# QCPower_Rev_A_Sht2_BLDC_Controller.net
KiCad netlist of a schematic drawn in Altium Designer
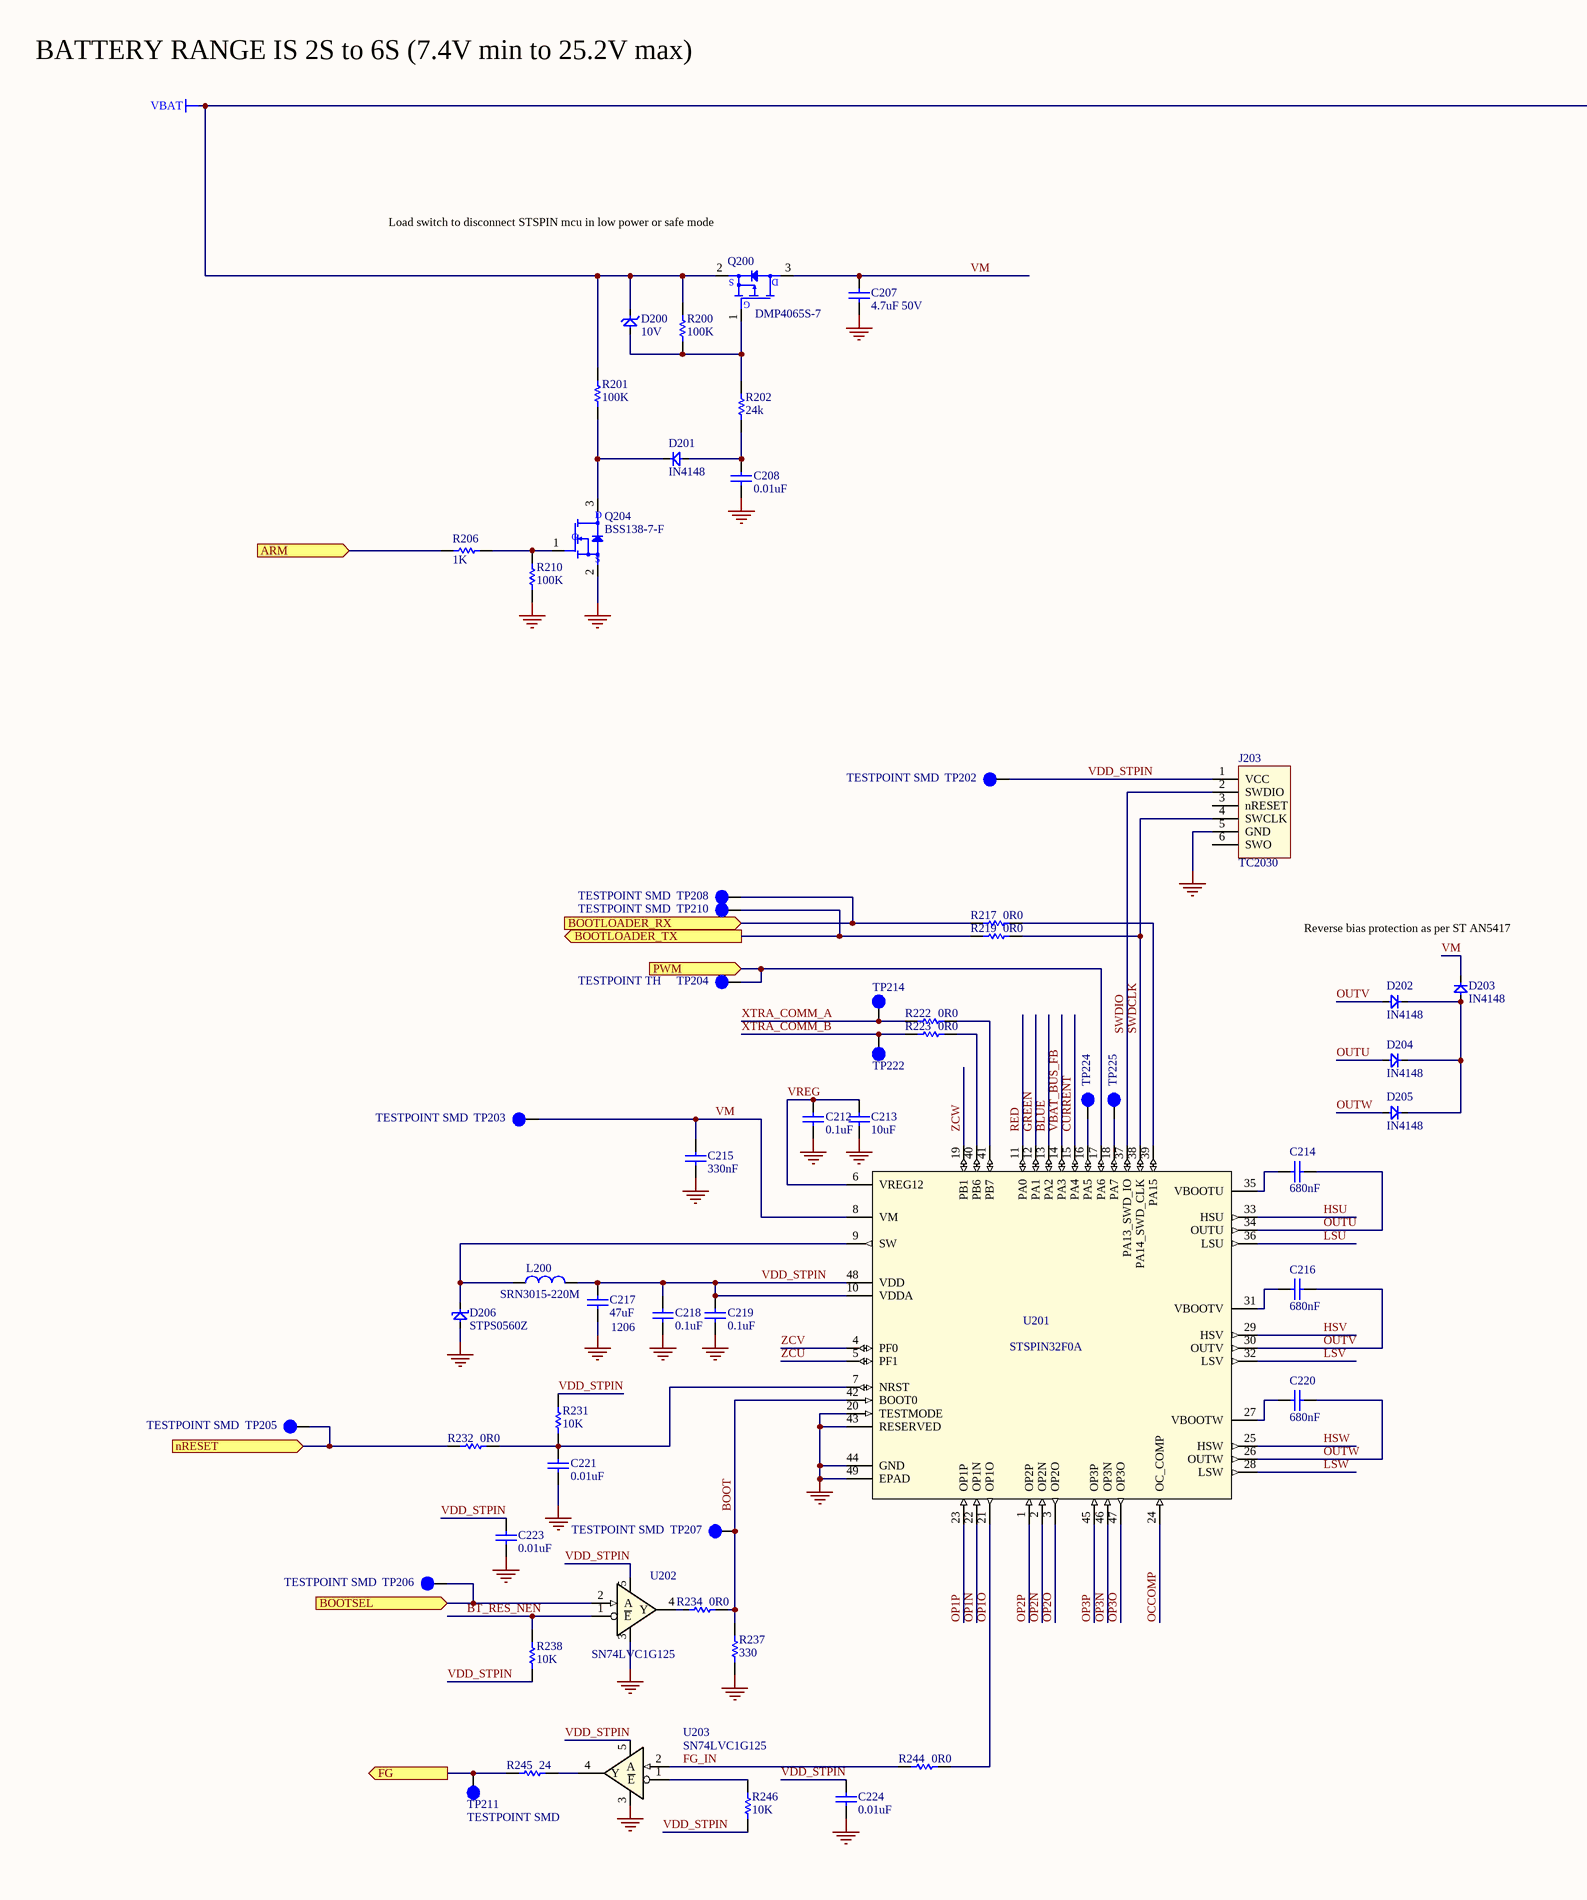
[diagram p0: QCPower Rev A Sht2 BLDC Controller.SchDoc, left]
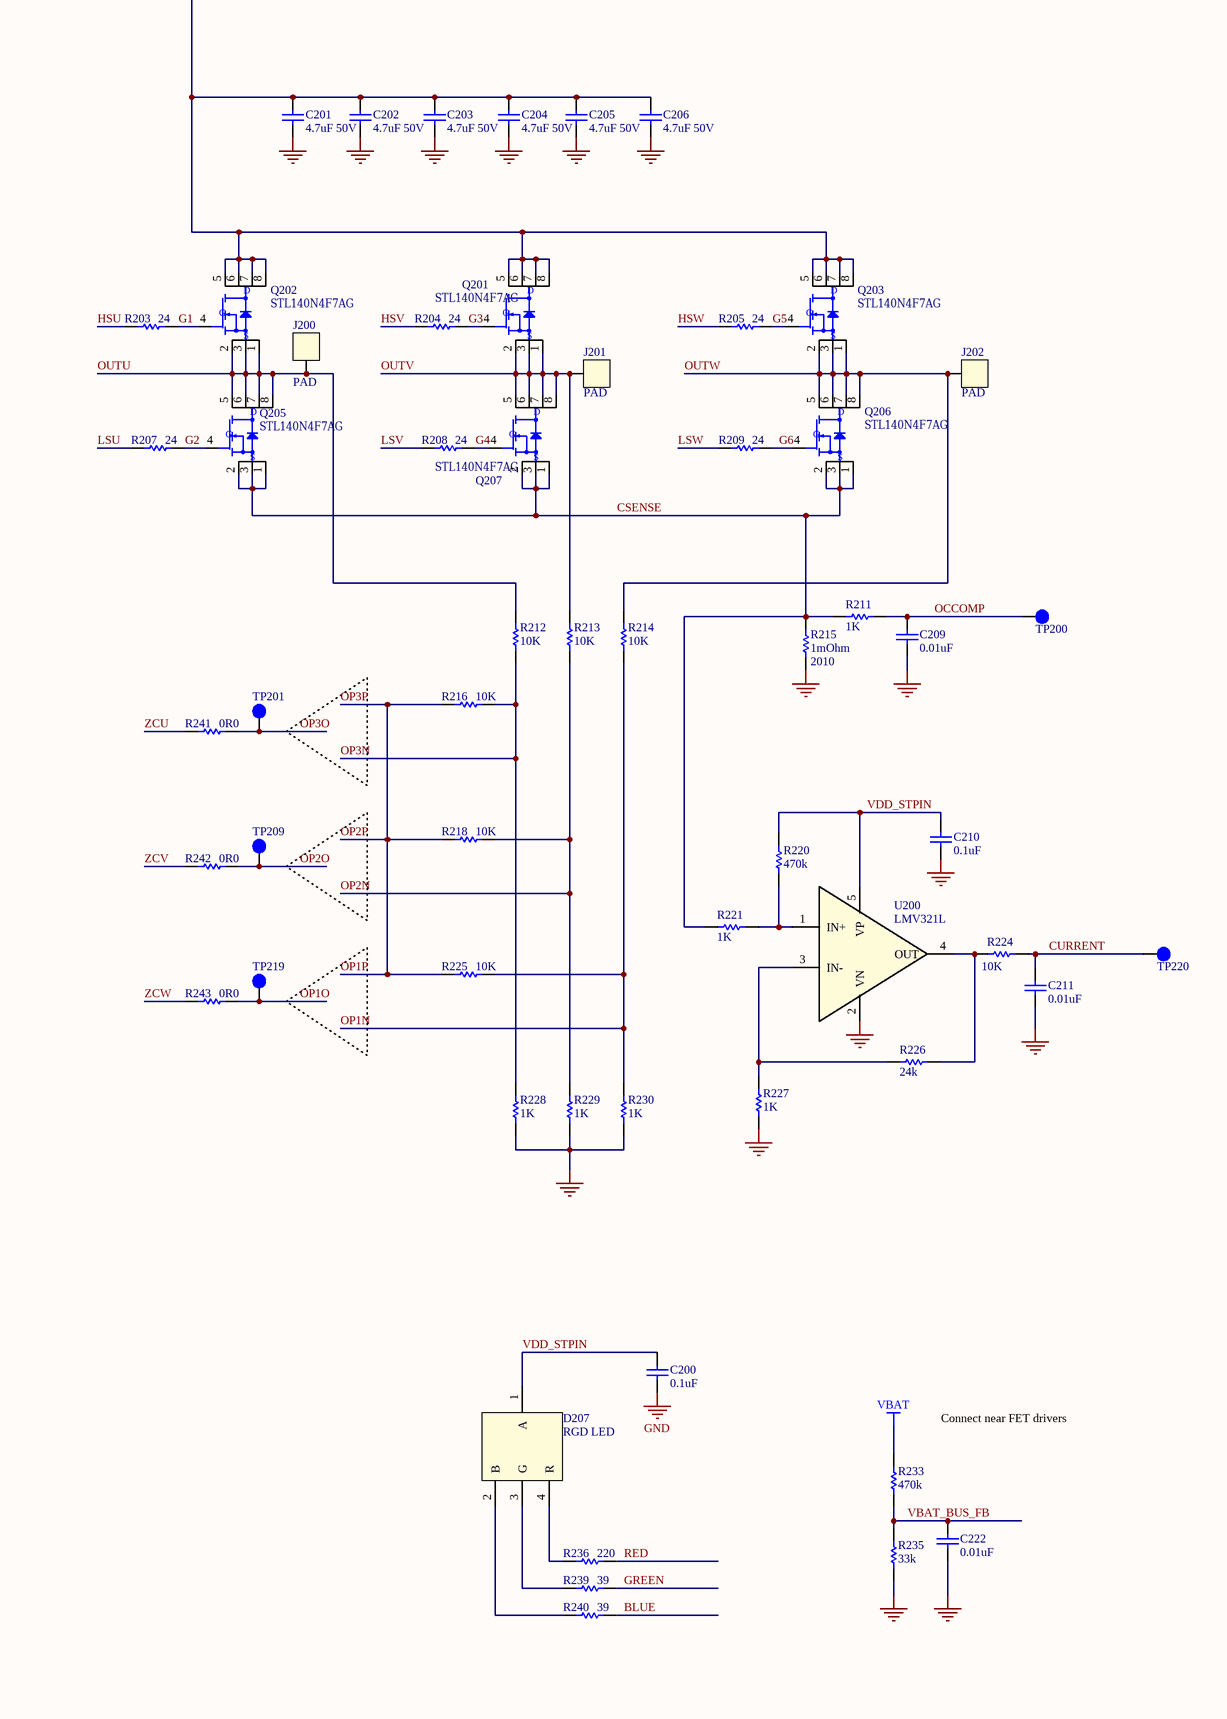
[diagram p1: QCPower Rev A Sht2 BLDC Controller.SchDoc, right]

(export (version "E")
  (design (tool "Eeschema 10.0.6"))
  (components
    (comp (ref "C200")
      (value "0.1uF")
      (footprint "SMD CAP 0402")
      (description "CAP CER 0.1UF 25V X7R 0402")
      (fields (field (name "2. MANUFACTURER PART NUMBER") "CC0402KRX7R8BB104"))
      (libsource (lib "SBCLib") (part "CAP MLCC SMD"))
    )
    (comp (ref "C201")
      (value "4.7uF 50V")
      (footprint "SMD CAP 0805")
      (description "CAP CER 4.7UF 50V X5R 0805")
      (fields (field (name "2. MANUFACTURER PART NUMBER") "CL21A475KBQNNNE"))
      (libsource (lib "SBCLib") (part "CAP MLCC SMD"))
    )
    (comp (ref "C202")
      (value "4.7uF 50V")
      (footprint "SMD CAP 0805")
      (description "CAP CER 4.7UF 50V X5R 0805")
      (fields (field (name "2. MANUFACTURER PART NUMBER") "CL21A475KBQNNNE"))
      (libsource (lib "SBCLib") (part "CAP MLCC SMD"))
    )
    (comp (ref "C203")
      (value "4.7uF 50V")
      (footprint "SMD CAP 0805")
      (description "CAP CER 4.7UF 50V X5R 0805")
      (fields (field (name "2. MANUFACTURER PART NUMBER") "CL21A475KBQNNNE"))
      (libsource (lib "SBCLib") (part "CAP MLCC SMD"))
    )
    (comp (ref "C204")
      (value "4.7uF 50V")
      (footprint "SMD CAP 0805")
      (description "CAP CER 4.7UF 50V X5R 0805")
      (fields (field (name "2. MANUFACTURER PART NUMBER") "CL21A475KBQNNNE"))
      (libsource (lib "SBCLib") (part "CAP MLCC SMD"))
    )
    (comp (ref "C205")
      (value "4.7uF 50V")
      (footprint "SMD CAP 0805")
      (description "CAP CER 4.7UF 50V X5R 0805")
      (fields (field (name "2. MANUFACTURER PART NUMBER") "CL21A475KBQNNNE"))
      (libsource (lib "SBCLib") (part "CAP MLCC SMD"))
    )
    (comp (ref "C206")
      (value "4.7uF 50V")
      (footprint "SMD CAP 0805")
      (description "CAP CER 4.7UF 50V X5R 0805")
      (fields (field (name "2. MANUFACTURER PART NUMBER") "CL21A475KBQNNNE"))
      (libsource (lib "SBCLib") (part "CAP MLCC SMD"))
    )
    (comp (ref "C207")
      (value "4.7uF 50V")
      (footprint "SMD CAP 0805")
      (description "CAP CER 4.7UF 50V X5R 0805")
      (fields (field (name "2. MANUFACTURER PART NUMBER") "CL21A475KBQNNNE"))
      (libsource (lib "SBCLib") (part "CAP MLCC SMD"))
    )
    (comp (ref "C208")
      (value "0.01uF")
      (footprint "SMD CAP 0402")
      (description "CAP CER 10000PF 16V X7R 0402")
      (fields (field (name "2. MANUFACTURER PART NUMBER") "0402B103K160CT"))
      (libsource (lib "SBCLib") (part "CAP MLCC SMD"))
    )
    (comp (ref "C209")
      (value "0.01uF")
      (footprint "SMD CAP 0402")
      (description "CAP CER 10000PF 16V X7R 0402")
      (fields (field (name "2. MANUFACTURER PART NUMBER") "0402B103K160CT"))
      (libsource (lib "SBCLib") (part "CAP MLCC SMD"))
    )
    (comp (ref "C210")
      (value "0.1uF")
      (footprint "SMD CAP 0402")
      (description "CAP CER 0.1UF 25V X7R 0402")
      (fields (field (name "2. MANUFACTURER PART NUMBER") "CC0402KRX7R8BB104"))
      (libsource (lib "SBCLib") (part "CAP MLCC SMD"))
    )
    (comp (ref "C211")
      (value "0.01uF")
      (footprint "SMD CAP 0402")
      (description "CAP CER 10000PF 16V X7R 0402")
      (fields (field (name "2. MANUFACTURER PART NUMBER") "0402B103K160CT"))
      (libsource (lib "SBCLib") (part "CAP MLCC SMD"))
    )
    (comp (ref "C212")
      (value "0.1uF")
      (footprint "SMD CAP 0402")
      (description "CAP CER 0.1UF 25V X7R 0402")
      (fields (field (name "2. MANUFACTURER PART NUMBER") "CC0402KRX7R8BB104"))
      (libsource (lib "SBCLib") (part "CAP MLCC SMD"))
    )
    (comp (ref "C213")
      (value "10uF")
      (footprint "SMD CAP 0805")
      (description "CAP CER 10UF 25V X5R 0805")
      (fields (field (name "2. MANUFACTURER PART NUMBER") "TMK212BBJ106KG-T"))
      (libsource (lib "SBCLib") (part "CAP MLCC SMD"))
    )
    (comp (ref "C214")
      (value "680nF")
      (footprint "SMD CAP 0603")
      (description "CAP CER 0.68UF 25V X7R 0603")
      (fields (field (name "2. MANUFACTURER PART NUMBER") "CGA3E1X7R1E684K080AC"))
      (libsource (lib "SBCLib") (part "CAP MLCC SMD"))
    )
    (comp (ref "C215")
      (value "330nF")
      (footprint "SMD CAP 0603")
      (description "CAP CER 0.33UF 50V X7R 0603")
      (fields (field (name "2. MANUFACTURER PART NUMBER") "C1608X7R1H334K080AC"))
      (libsource (lib "SBCLib") (part "CAP MLCC SMD"))
    )
    (comp (ref "C216")
      (value "680nF")
      (footprint "SMD CAP 0603")
      (description "CAP CER 0.68UF 25V X7R 0603")
      (fields (field (name "2. MANUFACTURER PART NUMBER") "CGA3E1X7R1E684K080AC"))
      (libsource (lib "SBCLib") (part "CAP MLCC SMD"))
    )
    (comp (ref "C217")
      (value "47uF")
      (footprint "SMD CAP 1206")
      (description "CAP CER 47UF 10V X5R 1206")
      (fields
        (field (name "2. MANUFACTURER PART NUMBER") "GRM31CR61A476ME15L")
        (field (name "4. PACKAGE") "1206")
      )
      (libsource (lib "SBCLib") (part "CAP MLCC SMD"))
    )
    (comp (ref "C218")
      (value "0.1uF")
      (footprint "SMD CAP 0402")
      (description "CAP CER 0.1UF 25V X7R 0402")
      (fields (field (name "2. MANUFACTURER PART NUMBER") "CC0402KRX7R8BB104"))
      (libsource (lib "SBCLib") (part "CAP MLCC SMD"))
    )
    (comp (ref "C219")
      (value "0.1uF")
      (footprint "SMD CAP 0402")
      (description "CAP CER 0.1UF 25V X7R 0402")
      (fields (field (name "2. MANUFACTURER PART NUMBER") "CC0402KRX7R8BB104"))
      (libsource (lib "SBCLib") (part "CAP MLCC SMD"))
    )
    (comp (ref "C220")
      (value "680nF")
      (footprint "SMD CAP 0603")
      (description "CAP CER 0.68UF 25V X7R 0603")
      (fields (field (name "2. MANUFACTURER PART NUMBER") "CGA3E1X7R1E684K080AC"))
      (libsource (lib "SBCLib") (part "CAP MLCC SMD"))
    )
    (comp (ref "C221")
      (value "0.01uF")
      (footprint "SMD CAP 0402")
      (description "CAP CER 10000PF 16V X7R 0402")
      (fields (field (name "2. MANUFACTURER PART NUMBER") "0402B103K160CT"))
      (libsource (lib "SBCLib") (part "CAP MLCC SMD"))
    )
    (comp (ref "C222")
      (value "0.01uF")
      (footprint "SMD CAP 0402")
      (description "CAP CER 10000PF 16V X7R 0402")
      (fields (field (name "2. MANUFACTURER PART NUMBER") "0402B103K160CT"))
      (libsource (lib "SBCLib") (part "CAP MLCC SMD"))
    )
    (comp (ref "C223")
      (value "0.01uF")
      (footprint "SMD CAP 0402")
      (description "CAP CER 10000PF 16V X7R 0402")
      (fields (field (name "2. MANUFACTURER PART NUMBER") "0402B103K160CT"))
      (libsource (lib "SBCLib") (part "CAP MLCC SMD"))
    )
    (comp (ref "C224")
      (value "0.01uF")
      (footprint "SMD CAP 0402")
      (description "CAP CER 10000PF 16V X7R 0402")
      (fields (field (name "2. MANUFACTURER PART NUMBER") "0402B103K160CT"))
      (libsource (lib "SBCLib") (part "CAP MLCC SMD"))
    )
    (comp (ref "D200")
      (value "10V")
      (footprint "DIODE SOD-523")
      (description "DIODE ZENER 10V 350MW SOD523")
      (fields (field (name "2. MANUFACTURER PART NUMBER") "BZT585B10T-7"))
      (libsource (lib "SBCLib") (part "DIODE ZENER"))
    )
    (comp (ref "D201")
      (value "IN4148")
      (footprint "DIODE SOD-523")
      (description "DIODE GEN PURP 75V 200MA SOD523F")
      (fields (field (name "2. MANUFACTURER PART NUMBER") "1N4148WT"))
      (libsource (lib "SBCLib") (part "DIODE STANDARD"))
    )
    (comp (ref "D202")
      (value "IN4148")
      (footprint "DIODE SOD-523")
      (description "DIODE GEN PURP 75V 200MA SOD523F")
      (fields (field (name "2. MANUFACTURER PART NUMBER") "1N4148WT"))
      (libsource (lib "SBCLib") (part "DIODE STANDARD"))
    )
    (comp (ref "D203")
      (value "IN4148")
      (footprint "DIODE SOD-523")
      (description "DIODE GEN PURP 75V 200MA SOD523F")
      (fields (field (name "2. MANUFACTURER PART NUMBER") "1N4148WT"))
      (libsource (lib "SBCLib") (part "DIODE STANDARD"))
    )
    (comp (ref "D204")
      (value "IN4148")
      (footprint "DIODE SOD-523")
      (description "DIODE GEN PURP 75V 200MA SOD523F")
      (fields (field (name "2. MANUFACTURER PART NUMBER") "1N4148WT"))
      (libsource (lib "SBCLib") (part "DIODE STANDARD"))
    )
    (comp (ref "D205")
      (value "IN4148")
      (footprint "DIODE SOD-523")
      (description "DIODE GEN PURP 75V 200MA SOD523F")
      (fields (field (name "2. MANUFACTURER PART NUMBER") "1N4148WT"))
      (libsource (lib "SBCLib") (part "DIODE STANDARD"))
    )
    (comp (ref "D206")
      (value "STPS0560Z")
      (footprint "DIODE SOD123")
      (description "DIODE SCHOTTKY 60V 500MA SOD123")
      (libsource (lib "SBCLib") (part "DIODE SCHOTTKY"))
    )
    (comp (ref "D207")
      (value "RGD LED")
      (footprint "PLCC-4 LED ASMB-MTB0-0A3A2")
      (description "LED RGB DIFFUSED 4PLCC SMD")
      (fields (field (name "2. MANUFACTURER PART NUMBER") "ASMB-MTB0-0A3A2"))
      (libsource (lib "SBCLib") (part "LED RGB DIFFUSED 4PLCC SMD"))
    )
    (comp (ref "J200")
      (value "PAD")
      (footprint "CONN SOLDER MOTOR")
      (description "CONN SOLDER MOTOR 7x5")
      (libsource (lib "SBCLib") (part "CONN SOLDER MOTOR 7x5"))
    )
    (comp (ref "J201")
      (value "PAD")
      (footprint "CONN SOLDER MOTOR")
      (description "CONN SOLDER MOTOR 7x5")
      (libsource (lib "") (part "CONN SOLDER MOTOR 7x5_1"))
    )
    (comp (ref "J202")
      (value "PAD")
      (footprint "CONN SOLDER MOTOR")
      (description "CONN SOLDER MOTOR 7x5")
      (libsource (lib "") (part "CONN SOLDER MOTOR 7x5_1"))
    )
    (comp (ref "J203")
      (value "TC2030")
      (footprint "tag-connect-6")
      (description "TC2030 PGM PADS")
      (fields (field (name "2. MANUFACTURER PART NUMBER") "NA"))
      (libsource (lib "MasterLiiiib") (part "TC2030"))
    )
    (comp (ref "L200")
      (value "SRN3015-220M")
      (footprint "INDUCTOR SRN3015-220M")
      (description "IND FIXED 22UH 600MA 622MOHM SMD")
      (libsource (lib "SBCLib") (part "INDUCTOR"))
    )
    (comp (ref "Q200")
      (value "DMP4065S-7")
      (footprint "SOT-23-3")
      (description "TRANS FET P-CH 40V 2.4A SOT23-3")
      (libsource (lib "SBCLib") (part "TRANS FET P-CH 40V 2.4A SOT23-3"))
    )
    (comp (ref "Q201")
      (value "STL140N4F7AG‎")
      (footprint "PowerFLAT 5x6")
      (description "MOSFET N-CH 40V 120A POWERFLAT")
      (libsource (lib "SBCLib") (part "TRANS FET N-CH 60V 145A 8PWRFLAT STL140N6F7"))
    )
    (comp (ref "Q202")
      (value "STL140N4F7AG‎")
      (footprint "PowerFLAT 5x6")
      (description "MOSFET N-CH 40V 120A POWERFLAT")
      (libsource (lib "SBCLib") (part "TRANS FET N-CH 60V 145A 8PWRFLAT STL140N6F7"))
    )
    (comp (ref "Q203")
      (value "STL140N4F7AG‎")
      (footprint "PowerFLAT 5x6")
      (description "MOSFET N-CH 40V 120A POWERFLAT")
      (libsource (lib "SBCLib") (part "TRANS FET N-CH 60V 145A 8PWRFLAT STL140N6F7"))
    )
    (comp (ref "Q204")
      (value "BSS138-7-F")
      (footprint "SOT-23-3")
      (description "TRANS FET N-CH 50V 200MA SOT23-3 BSS138-7-F")
      (libsource (lib "SBCLib") (part "TRANS FET N-CH 50V 200MA SOT23-3 BSS138-7-F"))
    )
    (comp (ref "Q205")
      (value "STL140N4F7AG‎")
      (footprint "PowerFLAT 5x6")
      (description "MOSFET N-CH 40V 120A POWERFLAT")
      (libsource (lib "SBCLib") (part "TRANS FET N-CH 60V 145A 8PWRFLAT STL140N6F7"))
    )
    (comp (ref "Q206")
      (value "STL140N4F7AG‎")
      (footprint "PowerFLAT 5x6")
      (description "MOSFET N-CH 40V 120A POWERFLAT")
      (libsource (lib "SBCLib") (part "TRANS FET N-CH 60V 145A 8PWRFLAT STL140N6F7"))
    )
    (comp (ref "Q207")
      (value "STL140N4F7AG‎")
      (footprint "PowerFLAT 5x6")
      (description "MOSFET N-CH 40V 120A POWERFLAT")
      (libsource (lib "SBCLib") (part "TRANS FET N-CH 60V 145A 8PWRFLAT STL140N6F7"))
    )
    (comp (ref "R200")
      (value "100K")
      (footprint "SMD RES 0402")
      (description "RES SMD 100K OHM 1% 1/16W 0402")
      (fields (field (name "2. MANUFACTURER PART NUMBER") "RC0402FR-07100KL"))
      (libsource (lib "SBCLib") (part "RES SMD"))
    )
    (comp (ref "R201")
      (value "100K")
      (footprint "SMD RES 0402")
      (description "RES SMD 100K OHM 1% 1/16W 0402")
      (fields (field (name "2. MANUFACTURER PART NUMBER") "RC0402FR-07100KL"))
      (libsource (lib "SBCLib") (part "RES SMD"))
    )
    (comp (ref "R202")
      (value "24k")
      (footprint "SMD RES 0402")
      (description "RES SMD 24K OHM 1% 1/16W 0402")
      (fields (field (name "2. MANUFACTURER PART NUMBER") "RC0402FR-0724KL"))
      (libsource (lib "SBCLib") (part "RES SMD"))
    )
    (comp (ref "R203")
      (value "24")
      (footprint "SMD RES 0402")
      (description "RES SMD 24 OHM 5% 1/10W 0402")
      (fields (field (name "2. MANUFACTURER PART NUMBER") "ERJ-2GEJ240X"))
      (libsource (lib "SBCLib") (part "RES SMD"))
    )
    (comp (ref "R204")
      (value "24")
      (footprint "SMD RES 0402")
      (description "RES SMD 24 OHM 5% 1/10W 0402")
      (fields (field (name "2. MANUFACTURER PART NUMBER") "ERJ-2GEJ240X"))
      (libsource (lib "SBCLib") (part "RES SMD"))
    )
    (comp (ref "R205")
      (value "24")
      (footprint "SMD RES 0402")
      (description "RES SMD 24 OHM 5% 1/10W 0402")
      (fields (field (name "2. MANUFACTURER PART NUMBER") "ERJ-2GEJ240X"))
      (libsource (lib "SBCLib") (part "RES SMD"))
    )
    (comp (ref "R206")
      (value "1K")
      (footprint "SMD RES 0402")
      (description "RES SMD 1K OHM 1% 1/16W 0402")
      (fields (field (name "2. MANUFACTURER PART NUMBER") "RC0402FR-071KL"))
      (libsource (lib "SBCLib") (part "RES SMD"))
    )
    (comp (ref "R207")
      (value "24")
      (footprint "SMD RES 0402")
      (description "RES SMD 24 OHM 5% 1/10W 0402")
      (fields (field (name "2. MANUFACTURER PART NUMBER") "ERJ-2GEJ240X"))
      (libsource (lib "SBCLib") (part "RES SMD"))
    )
    (comp (ref "R208")
      (value "24")
      (footprint "SMD RES 0402")
      (description "RES SMD 24 OHM 5% 1/10W 0402")
      (fields (field (name "2. MANUFACTURER PART NUMBER") "ERJ-2GEJ240X"))
      (libsource (lib "SBCLib") (part "RES SMD"))
    )
    (comp (ref "R209")
      (value "24")
      (footprint "SMD RES 0402")
      (description "RES SMD 24 OHM 5% 1/10W 0402")
      (fields (field (name "2. MANUFACTURER PART NUMBER") "ERJ-2GEJ240X"))
      (libsource (lib "SBCLib") (part "RES SMD"))
    )
    (comp (ref "R210")
      (value "100K")
      (footprint "SMD RES 0402")
      (description "RES SMD 100K OHM 1% 1/16W 0402")
      (fields (field (name "2. MANUFACTURER PART NUMBER") "RC0402FR-07100KL"))
      (libsource (lib "SBCLib") (part "RES SMD"))
    )
    (comp (ref "R211")
      (value "1K")
      (footprint "SMD RES 0402")
      (description "RES SMD 1K OHM 1% 1/16W 0402")
      (fields (field (name "2. MANUFACTURER PART NUMBER") "RC0402FR-071KL"))
      (libsource (lib "SBCLib") (part "RES SMD"))
    )
    (comp (ref "R212")
      (value "10K")
      (footprint "SMD RES 0402")
      (description "RES SMD 10K OHM 1% 1/16W 0402")
      (fields (field (name "2. MANUFACTURER PART NUMBER") "RC0402FR-0710KL"))
      (libsource (lib "SBCLib") (part "RES SMD"))
    )
    (comp (ref "R213")
      (value "10K")
      (footprint "SMD RES 0402")
      (description "RES SMD 10K OHM 1% 1/16W 0402")
      (fields (field (name "2. MANUFACTURER PART NUMBER") "RC0402FR-0710KL"))
      (libsource (lib "SBCLib") (part "RES SMD"))
    )
    (comp (ref "R214")
      (value "10K")
      (footprint "SMD RES 0402")
      (description "RES SMD 10K OHM 1% 1/16W 0402")
      (fields (field (name "2. MANUFACTURER PART NUMBER") "RC0402FR-0710KL"))
      (libsource (lib "SBCLib") (part "RES SMD"))
    )
    (comp (ref "R215")
      (value "1mOhm")
      (footprint "SMD RES 2010")
      (description "RES 0.001 OHM 1% 1.5W 2010")
      (fields
        (field (name "2. MANUFACTURER PART NUMBER") "CSNL2010FT1L00")
        (field (name "4. PACKAGE") "2010")
      )
      (libsource (lib "SBCLib") (part "RES SMD"))
    )
    (comp (ref "R216")
      (value "10K")
      (footprint "SMD RES 0402")
      (description "RES SMD 10K OHM 1% 1/16W 0402")
      (fields (field (name "2. MANUFACTURER PART NUMBER") "RC0402FR-0710KL"))
      (libsource (lib "SBCLib") (part "RES SMD"))
    )
    (comp (ref "R217")
      (value "0R0")
      (footprint "SMD RES 0402")
      (description "RES SMD 0 OHM JUMPER 1/16W 0402")
      (fields (field (name "2. MANUFACTURER PART NUMBER") "RC0402FR-070RL"))
      (libsource (lib "SBCLib") (part "RES SMD"))
    )
    (comp (ref "R218")
      (value "10K")
      (footprint "SMD RES 0402")
      (description "RES SMD 10K OHM 1% 1/16W 0402")
      (fields (field (name "2. MANUFACTURER PART NUMBER") "RC0402FR-0710KL"))
      (libsource (lib "SBCLib") (part "RES SMD"))
    )
    (comp (ref "R219")
      (value "0R0")
      (footprint "SMD RES 0402")
      (description "RES SMD 0 OHM JUMPER 1/16W 0402")
      (fields (field (name "2. MANUFACTURER PART NUMBER") "RC0402FR-070RL"))
      (libsource (lib "SBCLib") (part "RES SMD"))
    )
    (comp (ref "R220")
      (value "470k")
      (footprint "SMD RES 0402")
      (description "RES SMD 470K OHM 1% 1/16W 0402")
      (fields (field (name "2. MANUFACTURER PART NUMBER") "RC0402FR-07470KL"))
      (libsource (lib "SBCLib") (part "RES SMD"))
    )
    (comp (ref "R221")
      (value "1K")
      (footprint "SMD RES 0402")
      (description "RES SMD 1K OHM 1% 1/16W 0402")
      (fields (field (name "2. MANUFACTURER PART NUMBER") "RC0402FR-071KL"))
      (libsource (lib "SBCLib") (part "RES SMD"))
    )
    (comp (ref "R222")
      (value "0R0")
      (footprint "SMD RES 0402")
      (description "RES SMD 0 OHM JUMPER 1/16W 0402")
      (fields (field (name "2. MANUFACTURER PART NUMBER") "RC0402FR-070RL"))
      (libsource (lib "SBCLib") (part "RES SMD"))
    )
    (comp (ref "R223")
      (value "0R0")
      (footprint "SMD RES 0402")
      (description "RES SMD 0 OHM JUMPER 1/16W 0402")
      (fields (field (name "2. MANUFACTURER PART NUMBER") "RC0402FR-070RL"))
      (libsource (lib "SBCLib") (part "RES SMD"))
    )
    (comp (ref "R224")
      (value "10K")
      (footprint "SMD RES 0402")
      (description "RES SMD 10K OHM 1% 1/16W 0402")
      (fields (field (name "2. MANUFACTURER PART NUMBER") "RC0402FR-0710KL"))
      (libsource (lib "SBCLib") (part "RES SMD"))
    )
    (comp (ref "R225")
      (value "10K")
      (footprint "SMD RES 0402")
      (description "RES SMD 10K OHM 1% 1/16W 0402")
      (fields (field (name "2. MANUFACTURER PART NUMBER") "RC0402FR-0710KL"))
      (libsource (lib "SBCLib") (part "RES SMD"))
    )
    (comp (ref "R226")
      (value "24k")
      (footprint "SMD RES 0402")
      (description "RES SMD 24K OHM 1% 1/16W 0402")
      (fields (field (name "2. MANUFACTURER PART NUMBER") "RC0402FR-0724KL"))
      (libsource (lib "SBCLib") (part "RES SMD"))
    )
    (comp (ref "R227")
      (value "1K")
      (footprint "SMD RES 0402")
      (description "RES SMD 1K OHM 1% 1/16W 0402")
      (fields (field (name "2. MANUFACTURER PART NUMBER") "RC0402FR-071KL"))
      (libsource (lib "SBCLib") (part "RES SMD"))
    )
    (comp (ref "R228")
      (value "1K")
      (footprint "SMD RES 0402")
      (description "RES SMD 1K OHM 1% 1/16W 0402")
      (fields (field (name "2. MANUFACTURER PART NUMBER") "RC0402FR-071KL"))
      (libsource (lib "SBCLib") (part "RES SMD"))
    )
    (comp (ref "R229")
      (value "1K")
      (footprint "SMD RES 0402")
      (description "RES SMD 1K OHM 1% 1/16W 0402")
      (fields (field (name "2. MANUFACTURER PART NUMBER") "RC0402FR-071KL"))
      (libsource (lib "SBCLib") (part "RES SMD"))
    )
    (comp (ref "R230")
      (value "1K")
      (footprint "SMD RES 0402")
      (description "RES SMD 1K OHM 1% 1/16W 0402")
      (fields (field (name "2. MANUFACTURER PART NUMBER") "RC0402FR-071KL"))
      (libsource (lib "SBCLib") (part "RES SMD"))
    )
    (comp (ref "R231")
      (value "10K")
      (footprint "SMD RES 0402")
      (description "RES SMD 10K OHM 1% 1/16W 0402")
      (fields (field (name "2. MANUFACTURER PART NUMBER") "RC0402FR-0710KL"))
      (libsource (lib "SBCLib") (part "RES SMD"))
    )
    (comp (ref "R232")
      (value "0R0")
      (footprint "SMD RES 0402")
      (description "RES SMD 0 OHM JUMPER 1/16W 0402")
      (fields (field (name "2. MANUFACTURER PART NUMBER") "RC0402FR-070RL"))
      (libsource (lib "SBCLib") (part "RES SMD"))
    )
    (comp (ref "R233")
      (value "470k")
      (footprint "SMD RES 0402")
      (description "RES SMD 470K OHM 1% 1/16W 0402")
      (fields (field (name "2. MANUFACTURER PART NUMBER") "RC0402FR-07470KL"))
      (libsource (lib "SBCLib") (part "RES SMD"))
    )
    (comp (ref "R234")
      (value "0R0")
      (footprint "SMD RES 0402")
      (description "RES SMD 0 OHM JUMPER 1/16W 0402")
      (fields (field (name "2. MANUFACTURER PART NUMBER") "RC0402FR-070RL"))
      (libsource (lib "SBCLib") (part "RES SMD"))
    )
    (comp (ref "R235")
      (value "33k")
      (footprint "SMD RES 0402")
      (description "RES SMD 33K OHM 1% 1/16W 0402")
      (fields (field (name "2. MANUFACTURER PART NUMBER") "RC0402FR-0733KL"))
      (libsource (lib "SBCLib") (part "RES SMD"))
    )
    (comp (ref "R236")
      (value "220")
      (footprint "SMD RES 0402")
      (description "RES SMD 220 OHM 5% 1/16W 0402")
      (fields (field (name "2. MANUFACTURER PART NUMBER") "RC0402JR-07220RL"))
      (libsource (lib "SBCLib") (part "RES SMD"))
    )
    (comp (ref "R237")
      (value "330")
      (footprint "SMD RES 0402")
      (description "RES SMD 330 OHM 5% 1/16W 0402")
      (fields (field (name "2. MANUFACTURER PART NUMBER") "RC0402JR-07330RL"))
      (libsource (lib "SBCLib") (part "RES SMD"))
    )
    (comp (ref "R238")
      (value "10K")
      (footprint "SMD RES 0402")
      (description "RES SMD 10K OHM 1% 1/16W 0402")
      (fields (field (name "2. MANUFACTURER PART NUMBER") "RC0402FR-0710KL"))
      (libsource (lib "SBCLib") (part "RES SMD"))
    )
    (comp (ref "R239")
      (value "39")
      (footprint "SMD RES 0402")
      (description "RES SMD 39 OHM 5% 1/16W 0402")
      (fields (field (name "2. MANUFACTURER PART NUMBER") "RC0402JR-0739RL"))
      (libsource (lib "SBCLib") (part "RES SMD"))
    )
    (comp (ref "R240")
      (value "39")
      (footprint "SMD RES 0402")
      (description "RES SMD 39 OHM 5% 1/16W 0402")
      (fields (field (name "2. MANUFACTURER PART NUMBER") "RC0402JR-0739RL"))
      (libsource (lib "SBCLib") (part "RES SMD"))
    )
    (comp (ref "R241")
      (value "0R0")
      (footprint "SMD RES 0402")
      (description "RES SMD 0 OHM JUMPER 1/16W 0402")
      (fields (field (name "2. MANUFACTURER PART NUMBER") "RC0402FR-070RL"))
      (libsource (lib "SBCLib") (part "RES SMD"))
    )
    (comp (ref "R242")
      (value "0R0")
      (footprint "SMD RES 0402")
      (description "RES SMD 0 OHM JUMPER 1/16W 0402")
      (fields (field (name "2. MANUFACTURER PART NUMBER") "RC0402FR-070RL"))
      (libsource (lib "SBCLib") (part "RES SMD"))
    )
    (comp (ref "R243")
      (value "0R0")
      (footprint "SMD RES 0402")
      (description "RES SMD 0 OHM JUMPER 1/16W 0402")
      (fields (field (name "2. MANUFACTURER PART NUMBER") "RC0402FR-070RL"))
      (libsource (lib "SBCLib") (part "RES SMD"))
    )
    (comp (ref "R244")
      (value "0R0")
      (footprint "SMD RES 0402")
      (description "RES SMD 0 OHM JUMPER 1/16W 0402")
      (fields (field (name "2. MANUFACTURER PART NUMBER") "RC0402FR-070RL"))
      (libsource (lib "SBCLib") (part "RES SMD"))
    )
    (comp (ref "R245")
      (value "24")
      (footprint "SMD RES 0402")
      (description "RES SMD 24 OHM 5% 1/10W 0402")
      (fields (field (name "2. MANUFACTURER PART NUMBER") "ERJ-2GEJ240X"))
      (libsource (lib "SBCLib") (part "RES SMD"))
    )
    (comp (ref "R246")
      (value "10K")
      (footprint "SMD RES 0402")
      (description "RES SMD 10K OHM 1% 1/16W 0402")
      (fields (field (name "2. MANUFACTURER PART NUMBER") "RC0402FR-0710KL"))
      (libsource (lib "SBCLib") (part "RES SMD"))
    )
    (comp (ref "TP200")
      (value "TESTPOINT SMD")
      (footprint "TESTPOINT 0.5mm DIA")
      (description "TESTPOINT SMD PAD")
      (libsource (lib "SBCLib") (part "TESTPOINT PAD"))
    )
    (comp (ref "TP201")
      (value "TESTPOINT SMD")
      (footprint "TESTPOINT 0.5mm DIA")
      (description "TESTPOINT SMD PAD")
      (libsource (lib "SBCLib") (part "TESTPOINT PAD"))
    )
    (comp (ref "TP202")
      (value "TESTPOINT SMD")
      (footprint "TESTPOINT 0.5mm DIA")
      (description "TESTPOINT SMD PAD")
      (libsource (lib "SBCLib") (part "TESTPOINT PAD"))
    )
    (comp (ref "TP203")
      (value "TESTPOINT SMD")
      (footprint "TESTPOINT 0.5mm DIA")
      (description "TESTPOINT SMD PAD")
      (libsource (lib "SBCLib") (part "TESTPOINT PAD"))
    )
    (comp (ref "TP204")
      (value "TESTPOINT TH")
      (footprint "TESTPOINT TH")
      (description "TESTPOINT TH KEYSTONE")
      (fields (field (name "2. MANUFACTURER PART NUMBER") "5002"))
      (libsource (lib "SBCLib") (part "TESTPOINT TH"))
    )
    (comp (ref "TP205")
      (value "TESTPOINT SMD")
      (footprint "TESTPOINT 0.5mm DIA")
      (description "TESTPOINT SMD PAD")
      (libsource (lib "SBCLib") (part "TESTPOINT PAD"))
    )
    (comp (ref "TP206")
      (value "TESTPOINT SMD")
      (footprint "TESTPOINT 0.5mm DIA")
      (description "TESTPOINT SMD PAD")
      (libsource (lib "SBCLib") (part "TESTPOINT PAD"))
    )
    (comp (ref "TP207")
      (value "TESTPOINT SMD")
      (footprint "TESTPOINT 0.5mm DIA")
      (description "TESTPOINT SMD PAD")
      (libsource (lib "SBCLib") (part "TESTPOINT PAD"))
    )
    (comp (ref "TP208")
      (value "TESTPOINT SMD")
      (footprint "TESTPOINT 0.5mm DIA")
      (description "TESTPOINT SMD PAD")
      (libsource (lib "SBCLib") (part "TESTPOINT PAD"))
    )
    (comp (ref "TP209")
      (value "TESTPOINT SMD")
      (footprint "TESTPOINT 0.5mm DIA")
      (description "TESTPOINT SMD PAD")
      (libsource (lib "SBCLib") (part "TESTPOINT PAD"))
    )
    (comp (ref "TP210")
      (value "TESTPOINT SMD")
      (footprint "TESTPOINT 0.5mm DIA")
      (description "TESTPOINT SMD PAD")
      (libsource (lib "SBCLib") (part "TESTPOINT PAD"))
    )
    (comp (ref "TP211")
      (value "TESTPOINT SMD")
      (footprint "TESTPOINT 0.5mm DIA")
      (description "TESTPOINT SMD PAD")
      (libsource (lib "SBCLib") (part "TESTPOINT PAD"))
    )
    (comp (ref "TP214")
      (value "TESTPOINT SMD")
      (footprint "TESTPOINT 0.5mm DIA")
      (description "TESTPOINT SMD PAD")
      (libsource (lib "SBCLib") (part "TESTPOINT PAD"))
    )
    (comp (ref "TP219")
      (value "TESTPOINT SMD")
      (footprint "TESTPOINT 0.5mm DIA")
      (description "TESTPOINT SMD PAD")
      (libsource (lib "SBCLib") (part "TESTPOINT PAD"))
    )
    (comp (ref "TP220")
      (value "TESTPOINT SMD")
      (footprint "TESTPOINT 0.5mm DIA")
      (description "TESTPOINT SMD PAD")
      (libsource (lib "SBCLib") (part "TESTPOINT PAD"))
    )
    (comp (ref "TP222")
      (value "TESTPOINT SMD")
      (footprint "TESTPOINT 0.5mm DIA")
      (description "TESTPOINT SMD PAD")
      (libsource (lib "SBCLib") (part "TESTPOINT PAD"))
    )
    (comp (ref "TP224")
      (value "TESTPOINT SMD")
      (footprint "TESTPOINT 0.5mm DIA")
      (description "TESTPOINT SMD PAD")
      (libsource (lib "SBCLib") (part "TESTPOINT PAD"))
    )
    (comp (ref "TP225")
      (value "TESTPOINT SMD")
      (footprint "TESTPOINT 0.5mm DIA")
      (description "TESTPOINT SMD PAD")
      (libsource (lib "SBCLib") (part "TESTPOINT PAD"))
    )
    (comp (ref "U200")
      (value "LMV321L")
      (footprint "SOT-23-5")
      (description "IC OPAMP GP 1 CIRCUIT SOT23-5")
      (fields (field (name "2. MANUFACTURER PART NUMBER") "LMV321LILT"))
      (libsource (lib "SBCLib") (part "IC OPAMP GP 1 CIRCUIT SOT23-5"))
    )
    (comp (ref "U201")
      (value "STSPIN32F0A")
      (footprint "VQFN-48 7x7")
      (description "IC BLDC CONTROLLER STSPIN32F0A")
      (libsource (lib "SBCLib") (part "IC BLDC CONTROLLER STSPIN32F0A"))
    )
    (comp (ref "U202")
      (value "SN74LVC1G125")
      (footprint "SC70-5")
      (description "IC BUF TRI-STATE NON-INVERT 5.5V SC70-5")
      (fields (field (name "2. MANUFACTURER PART NUMBER") "SN74LVC1G125DCKR"))
      (libsource (lib "SBCLib") (part "IC BUF TRI-STATE NON-INVERT 5.5V SC70-5"))
    )
    (comp (ref "U203")
      (value "SN74LVC1G125")
      (footprint "SC70-5")
      (description "IC BUF TRI-STATE NON-INVERT 5.5V SC70-5")
      (fields (field (name "2. MANUFACTURER PART NUMBER") "SN74LVC1G125DCKR"))
      (libsource (lib "SBCLib") (part "IC BUF TRI-STATE NON-INVERT 5.5V SC70-5"))
    )
  )
  (nets
    (net (code "1") (name "/ARM") (class "Default")
      (node (ref "R206") (pin "2") (pinfunction "2_2") (pintype "passive"))
    )
    (net (code "2") (name "/BLUE") (class "Default")
      (node (ref "R240") (pin "2") (pinfunction "2_2") (pintype "passive"))
      (node (ref "U201") (pin "13") (pinfunction "PA2_13") (pintype "bidirectional"))
    )
    (net (code "3") (name "/BOOT") (class "Default")
      (node (ref "R234") (pin "2") (pinfunction "2_2") (pintype "passive"))
      (node (ref "R237") (pin "2") (pinfunction "2_2") (pintype "passive"))
      (node (ref "TP207") (pin "1") (pinfunction "1_1") (pintype "passive"))
      (node (ref "U201") (pin "42") (pinfunction "BOOT0_42") (pintype "input"))
    )
    (net (code "4") (name "/BOOTLOADER_RX") (class "Default")
      (node (ref "R217") (pin "1") (pinfunction "1_1") (pintype "passive"))
      (node (ref "TP208") (pin "1") (pinfunction "1_1") (pintype "passive"))
    )
    (net (code "5") (name "/BOOTLOADER_TX") (class "Default")
      (node (ref "R219") (pin "1") (pinfunction "1_1") (pintype "passive"))
      (node (ref "TP210") (pin "1") (pinfunction "1_1") (pintype "passive"))
    )
    (net (code "6") (name "/BOOTSEL") (class "Default")
      (node (ref "TP206") (pin "1") (pinfunction "1_1") (pintype "passive"))
      (node (ref "U202") (pin "2") (pinfunction "A_2") (pintype "input"))
    )
    (net (code "7") (name "/BT_RES_NEN") (class "Default")
      (node (ref "R238") (pin "1") (pinfunction "1_1") (pintype "passive"))
      (node (ref "U202") (pin "1") (pinfunction "~{E}_1") (pintype "passive"))
    )
    (net (code "8") (name "/CSENSE") (class "Default")
      (node (ref "Q205") (pin "1") (pinfunction "S_1") (pintype "passive"))
      (node (ref "Q205") (pin "2") (pinfunction "S_2") (pintype "passive"))
      (node (ref "Q205") (pin "3") (pinfunction "S_3") (pintype "passive"))
      (node (ref "Q206") (pin "1") (pinfunction "S_1") (pintype "passive"))
      (node (ref "Q206") (pin "2") (pinfunction "S_2") (pintype "passive"))
      (node (ref "Q206") (pin "3") (pinfunction "S_3") (pintype "passive"))
      (node (ref "Q207") (pin "1") (pinfunction "S_1") (pintype "passive"))
      (node (ref "Q207") (pin "2") (pinfunction "S_2") (pintype "passive"))
      (node (ref "Q207") (pin "3") (pinfunction "S_3") (pintype "passive"))
      (node (ref "R211") (pin "2") (pinfunction "2_2") (pintype "passive"))
      (node (ref "R215") (pin "2") (pinfunction "2_2") (pintype "passive"))
      (node (ref "R221") (pin "2") (pinfunction "2_2") (pintype "passive"))
    )
    (net (code "9") (name "/CURRENT") (class "Default")
      (node (ref "C211") (pin "1") (pinfunction "1_1") (pintype "passive"))
      (node (ref "R224") (pin "2") (pinfunction "2_2") (pintype "passive"))
      (node (ref "TP220") (pin "1") (pinfunction "1_1") (pintype "passive"))
      (node (ref "U201") (pin "15") (pinfunction "PA4_15") (pintype "bidirectional"))
    )
    (net (code "10") (name "/FG") (class "Default")
      (node (ref "R245") (pin "1") (pinfunction "1_1") (pintype "passive"))
      (node (ref "TP211") (pin "1") (pinfunction "1_1") (pintype "passive"))
    )
    (net (code "11") (name "/FG_IN") (class "Default")
      (node (ref "R244") (pin "1") (pinfunction "1_1") (pintype "passive"))
      (node (ref "U203") (pin "2") (pinfunction "A_2") (pintype "input"))
    )
    (net (code "12") (name "/G1") (class "Default")
      (node (ref "Q202") (pin "4") (pinfunction "G_4") (pintype "passive"))
      (node (ref "R203") (pin "2") (pinfunction "2_2") (pintype "passive"))
    )
    (net (code "13") (name "/G2") (class "Default")
      (node (ref "Q205") (pin "4") (pinfunction "G_4") (pintype "passive"))
      (node (ref "R207") (pin "2") (pinfunction "2_2") (pintype "passive"))
    )
    (net (code "14") (name "/G3") (class "Default")
      (node (ref "Q201") (pin "4") (pinfunction "G_4") (pintype "passive"))
      (node (ref "R204") (pin "2") (pinfunction "2_2") (pintype "passive"))
    )
    (net (code "15") (name "/G4") (class "Default")
      (node (ref "Q207") (pin "4") (pinfunction "G_4") (pintype "passive"))
      (node (ref "R208") (pin "2") (pinfunction "2_2") (pintype "passive"))
    )
    (net (code "16") (name "/G5") (class "Default")
      (node (ref "Q203") (pin "4") (pinfunction "G_4") (pintype "passive"))
      (node (ref "R205") (pin "2") (pinfunction "2_2") (pintype "passive"))
    )
    (net (code "17") (name "/G6") (class "Default")
      (node (ref "Q206") (pin "4") (pinfunction "G_4") (pintype "passive"))
      (node (ref "R209") (pin "2") (pinfunction "2_2") (pintype "passive"))
    )
    (net (code "18") (name "/GREEN") (class "Default")
      (node (ref "R239") (pin "2") (pinfunction "2_2") (pintype "passive"))
      (node (ref "U201") (pin "12") (pinfunction "PA1_12") (pintype "bidirectional"))
    )
    (net (code "19") (name "/HSU") (class "Default")
      (node (ref "R203") (pin "1") (pinfunction "1_1") (pintype "passive"))
      (node (ref "U201") (pin "33") (pinfunction "HSU_33") (pintype "output"))
    )
    (net (code "20") (name "/HSV") (class "Default")
      (node (ref "R204") (pin "1") (pinfunction "1_1") (pintype "passive"))
      (node (ref "U201") (pin "29") (pinfunction "HSV_29") (pintype "output"))
    )
    (net (code "21") (name "/HSW") (class "Default")
      (node (ref "R205") (pin "1") (pinfunction "1_1") (pintype "passive"))
      (node (ref "U201") (pin "25") (pinfunction "HSW_25") (pintype "output"))
    )
    (net (code "22") (name "/LSU") (class "Default")
      (node (ref "R207") (pin "1") (pinfunction "1_1") (pintype "passive"))
      (node (ref "U201") (pin "36") (pinfunction "LSU_36") (pintype "output"))
    )
    (net (code "23") (name "/LSV") (class "Default")
      (node (ref "R208") (pin "1") (pinfunction "1_1") (pintype "passive"))
      (node (ref "U201") (pin "32") (pinfunction "LSV_32") (pintype "output"))
    )
    (net (code "24") (name "/LSW") (class "Default")
      (node (ref "R209") (pin "1") (pinfunction "1_1") (pintype "passive"))
      (node (ref "U201") (pin "28") (pinfunction "LSW_28") (pintype "output"))
    )
    (net (code "25") (name "/OCCOMP") (class "Default")
      (node (ref "C209") (pin "1") (pinfunction "1_1") (pintype "passive"))
      (node (ref "R211") (pin "1") (pinfunction "1_1") (pintype "passive"))
      (node (ref "TP200") (pin "1") (pinfunction "1_1") (pintype "passive"))
      (node (ref "U201") (pin "24") (pinfunction "OC_COMP_24") (pintype "input"))
    )
    (net (code "26") (name "/OP1N") (class "Default")
      (node (ref "R214") (pin "2") (pinfunction "2_2") (pintype "passive"))
      (node (ref "R225") (pin "1") (pinfunction "1_1") (pintype "passive"))
      (node (ref "R230") (pin "2") (pinfunction "2_2") (pintype "passive"))
      (node (ref "U201") (pin "22") (pinfunction "OP1N_22") (pintype "input"))
    )
    (net (code "27") (name "/OP1O") (class "Default")
      (node (ref "R243") (pin "2") (pinfunction "2_2") (pintype "passive"))
      (node (ref "R244") (pin "2") (pinfunction "2_2") (pintype "passive"))
      (node (ref "TP219") (pin "1") (pinfunction "1_1") (pintype "passive"))
      (node (ref "U201") (pin "21") (pinfunction "OP1O_21") (pintype "output"))
    )
    (net (code "28") (name "/OP1P") (class "Default")
      (node (ref "R216") (pin "2") (pinfunction "2_2") (pintype "passive"))
      (node (ref "R218") (pin "2") (pinfunction "2_2") (pintype "passive"))
      (node (ref "R225") (pin "2") (pinfunction "2_2") (pintype "passive"))
      (node (ref "U201") (pin "1") (pinfunction "OP2P_1") (pintype "input"))
      (node (ref "U201") (pin "23") (pinfunction "OP1P_23") (pintype "input"))
      (node (ref "U201") (pin "45") (pinfunction "OP3P_45") (pintype "input"))
    )
    (net (code "29") (name "/OP2N") (class "Default")
      (node (ref "R213") (pin "2") (pinfunction "2_2") (pintype "passive"))
      (node (ref "R218") (pin "1") (pinfunction "1_1") (pintype "passive"))
      (node (ref "R229") (pin "2") (pinfunction "2_2") (pintype "passive"))
      (node (ref "U201") (pin "2") (pinfunction "OP2N_2") (pintype "input"))
    )
    (net (code "30") (name "/OP2O") (class "Default")
      (node (ref "R242") (pin "2") (pinfunction "2_2") (pintype "passive"))
      (node (ref "TP209") (pin "1") (pinfunction "1_1") (pintype "passive"))
      (node (ref "U201") (pin "3") (pinfunction "OP2O_3") (pintype "output"))
    )
    (net (code "31") (name "/OP3N") (class "Default")
      (node (ref "R212") (pin "2") (pinfunction "2_2") (pintype "passive"))
      (node (ref "R216") (pin "1") (pinfunction "1_1") (pintype "passive"))
      (node (ref "R228") (pin "2") (pinfunction "2_2") (pintype "passive"))
      (node (ref "U201") (pin "46") (pinfunction "OP3N_46") (pintype "input"))
    )
    (net (code "32") (name "/OP3O") (class "Default")
      (node (ref "R241") (pin "2") (pinfunction "2_2") (pintype "passive"))
      (node (ref "TP201") (pin "1") (pinfunction "1_1") (pintype "passive"))
      (node (ref "U201") (pin "47") (pinfunction "OP3O_47") (pintype "output"))
    )
    (net (code "33") (name "/OUTU") (class "Default")
      (node (ref "C214") (pin "2") (pinfunction "2_2") (pintype "passive"))
      (node (ref "D204") (pin "A") (pinfunction "A_A") (pintype "passive"))
      (node (ref "J200") (pin "1") (pinfunction "1_1") (pintype "passive"))
      (node (ref "Q202") (pin "1") (pinfunction "S_1") (pintype "passive"))
      (node (ref "Q202") (pin "2") (pinfunction "S_2") (pintype "passive"))
      (node (ref "Q202") (pin "3") (pinfunction "S_3") (pintype "passive"))
      (node (ref "Q205") (pin "5") (pinfunction "D_5") (pintype "passive"))
      (node (ref "Q205") (pin "6") (pinfunction "D_6") (pintype "passive"))
      (node (ref "Q205") (pin "7") (pinfunction "D_7") (pintype "passive"))
      (node (ref "Q205") (pin "8") (pinfunction "D_8") (pintype "passive"))
      (node (ref "R212") (pin "1") (pinfunction "1_1") (pintype "passive"))
      (node (ref "U201") (pin "34") (pinfunction "OUTU_34") (pintype "output"))
    )
    (net (code "34") (name "/OUTV") (class "Default")
      (node (ref "C216") (pin "2") (pinfunction "2_2") (pintype "passive"))
      (node (ref "D202") (pin "A") (pinfunction "A_A") (pintype "passive"))
      (node (ref "J201") (pin "1") (pinfunction "1_1") (pintype "passive"))
      (node (ref "Q201") (pin "1") (pinfunction "S_1") (pintype "passive"))
      (node (ref "Q201") (pin "2") (pinfunction "S_2") (pintype "passive"))
      (node (ref "Q201") (pin "3") (pinfunction "S_3") (pintype "passive"))
      (node (ref "Q207") (pin "5") (pinfunction "D_5") (pintype "passive"))
      (node (ref "Q207") (pin "6") (pinfunction "D_6") (pintype "passive"))
      (node (ref "Q207") (pin "7") (pinfunction "D_7") (pintype "passive"))
      (node (ref "Q207") (pin "8") (pinfunction "D_8") (pintype "passive"))
      (node (ref "R213") (pin "1") (pinfunction "1_1") (pintype "passive"))
      (node (ref "U201") (pin "30") (pinfunction "OUTV_30") (pintype "output"))
    )
    (net (code "35") (name "/OUTW") (class "Default")
      (node (ref "C220") (pin "2") (pinfunction "2_2") (pintype "passive"))
      (node (ref "D205") (pin "A") (pinfunction "A_A") (pintype "passive"))
      (node (ref "J202") (pin "1") (pinfunction "1_1") (pintype "passive"))
      (node (ref "Q203") (pin "1") (pinfunction "S_1") (pintype "passive"))
      (node (ref "Q203") (pin "2") (pinfunction "S_2") (pintype "passive"))
      (node (ref "Q203") (pin "3") (pinfunction "S_3") (pintype "passive"))
      (node (ref "Q206") (pin "5") (pinfunction "D_5") (pintype "passive"))
      (node (ref "Q206") (pin "6") (pinfunction "D_6") (pintype "passive"))
      (node (ref "Q206") (pin "7") (pinfunction "D_7") (pintype "passive"))
      (node (ref "Q206") (pin "8") (pinfunction "D_8") (pintype "passive"))
      (node (ref "R214") (pin "1") (pinfunction "1_1") (pintype "passive"))
      (node (ref "U201") (pin "26") (pinfunction "OUTW_26") (pintype "output"))
    )
    (net (code "36") (name "/PWM") (class "Default")
      (node (ref "TP204") (pin "1") (pinfunction "1_1") (pintype "passive"))
      (node (ref "U201") (pin "17") (pinfunction "PA6_17") (pintype "bidirectional"))
    )
    (net (code "37") (name "/RED") (class "Default")
      (node (ref "R236") (pin "2") (pinfunction "2_2") (pintype "passive"))
      (node (ref "U201") (pin "11") (pinfunction "PA0_11") (pintype "bidirectional"))
    )
    (net (code "38") (name "/SWDCLK") (class "Default")
      (node (ref "J203") (pin "4") (pinfunction "SWCLK_4") (pintype "passive"))
      (node (ref "R219") (pin "2") (pinfunction "2_2") (pintype "passive"))
      (node (ref "U201") (pin "38") (pinfunction "PA14_SWD_CLK_38") (pintype "bidirectional"))
    )
    (net (code "39") (name "/SWDIO") (class "Default")
      (node (ref "J203") (pin "2") (pinfunction "SWDIO_2") (pintype "passive"))
      (node (ref "U201") (pin "37") (pinfunction "PA13_SWD_IO_37") (pintype "bidirectional"))
    )
    (net (code "40") (name "/VBAT_BUS_FB") (class "Default")
      (node (ref "C222") (pin "1") (pinfunction "1_1") (pintype "passive"))
      (node (ref "R233") (pin "2") (pinfunction "2_2") (pintype "passive"))
      (node (ref "R235") (pin "1") (pinfunction "1_1") (pintype "passive"))
      (node (ref "U201") (pin "14") (pinfunction "PA3_14") (pintype "bidirectional"))
    )
    (net (code "41") (name "/VDD_STPIN") (class "Default")
      (node (ref "C200") (pin "2") (pinfunction "2_2") (pintype "passive"))
      (node (ref "C210") (pin "2") (pinfunction "2_2") (pintype "passive"))
      (node (ref "C217") (pin "1") (pinfunction "1_1") (pintype "passive"))
      (node (ref "C218") (pin "2") (pinfunction "2_2") (pintype "passive"))
      (node (ref "C219") (pin "2") (pinfunction "2_2") (pintype "passive"))
      (node (ref "C223") (pin "1") (pinfunction "1_1") (pintype "passive"))
      (node (ref "C224") (pin "1") (pinfunction "1_1") (pintype "passive"))
      (node (ref "D207") (pin "1") (pinfunction "A_1") (pintype "passive"))
      (node (ref "J203") (pin "1") (pinfunction "VCC_1") (pintype "passive"))
      (node (ref "L200") (pin "2") (pinfunction "2_2") (pintype "passive"))
      (node (ref "R220") (pin "1") (pinfunction "1_1") (pintype "passive"))
      (node (ref "R231") (pin "1") (pinfunction "1_1") (pintype "passive"))
      (node (ref "R238") (pin "2") (pinfunction "2_2") (pintype "passive"))
      (node (ref "R246") (pin "2") (pinfunction "2_2") (pintype "passive"))
      (node (ref "TP202") (pin "1") (pinfunction "1_1") (pintype "passive"))
      (node (ref "U200") (pin "5") (pinfunction "VP_5") (pintype "passive"))
      (node (ref "U201") (pin "10") (pinfunction "VDDA_10") (pintype "power_in"))
      (node (ref "U201") (pin "48") (pinfunction "VDD_48") (pintype "power_in"))
      (node (ref "U202") (pin "5") (pinfunction "VCC_5") (pintype "passive"))
      (node (ref "U203") (pin "5") (pinfunction "VCC_5") (pintype "passive"))
    )
    (net (code "42") (name "/VM") (class "Default")
      (node (ref "C207") (pin "1") (pinfunction "1_1") (pintype "passive"))
      (node (ref "C215") (pin "1") (pinfunction "1_1") (pintype "passive"))
      (node (ref "D203") (pin "K") (pinfunction "K_K") (pintype "passive"))
      (node (ref "Q200") (pin "3") (pinfunction "3_3") (pintype "passive"))
      (node (ref "TP203") (pin "1") (pinfunction "1_1") (pintype "passive"))
      (node (ref "U201") (pin "8") (pinfunction "VM_8") (pintype "power_in"))
    )
    (net (code "43") (name "/VREG") (class "Default")
      (node (ref "C212") (pin "2") (pinfunction "2_2") (pintype "passive"))
      (node (ref "C213") (pin "1") (pinfunction "1_1") (pintype "passive"))
      (node (ref "U201") (pin "6") (pinfunction "VREG12_6") (pintype "power_in"))
    )
    (net (code "44") (name "/XTRA_COMM_A") (class "Default")
      (node (ref "R222") (pin "1") (pinfunction "1_1") (pintype "passive"))
      (node (ref "TP214") (pin "1") (pinfunction "1_1") (pintype "passive"))
    )
    (net (code "45") (name "/XTRA_COMM_B") (class "Default")
      (node (ref "R223") (pin "1") (pinfunction "1_1") (pintype "passive"))
      (node (ref "TP222") (pin "1") (pinfunction "1_1") (pintype "passive"))
    )
    (net (code "46") (name "/ZCU") (class "Default")
      (node (ref "R241") (pin "1") (pinfunction "1_1") (pintype "passive"))
      (node (ref "U201") (pin "5") (pinfunction "PF1_5") (pintype "bidirectional"))
    )
    (net (code "47") (name "/ZCV") (class "Default")
      (node (ref "R242") (pin "1") (pinfunction "1_1") (pintype "passive"))
      (node (ref "U201") (pin "4") (pinfunction "PF0_4") (pintype "bidirectional"))
    )
    (net (code "48") (name "/ZCW") (class "Default")
      (node (ref "R243") (pin "1") (pinfunction "1_1") (pintype "passive"))
      (node (ref "U201") (pin "19") (pinfunction "PB1_19") (pintype "bidirectional"))
    )
    (net (code "49") (name "/nRESET") (class "Default")
      (node (ref "R232") (pin "1") (pinfunction "1_1") (pintype "passive"))
      (node (ref "TP205") (pin "1") (pinfunction "1_1") (pintype "passive"))
    )
    (net (code "50") (name "GND") (class "Default")
      (node (ref "C200") (pin "1") (pinfunction "1_1") (pintype "passive"))
      (node (ref "C201") (pin "2") (pinfunction "2_2") (pintype "passive"))
      (node (ref "C202") (pin "2") (pinfunction "2_2") (pintype "passive"))
      (node (ref "C203") (pin "2") (pinfunction "2_2") (pintype "passive"))
      (node (ref "C204") (pin "2") (pinfunction "2_2") (pintype "passive"))
      (node (ref "C205") (pin "2") (pinfunction "2_2") (pintype "passive"))
      (node (ref "C206") (pin "2") (pinfunction "2_2") (pintype "passive"))
      (node (ref "C207") (pin "2") (pinfunction "2_2") (pintype "passive"))
      (node (ref "C208") (pin "2") (pinfunction "2_2") (pintype "passive"))
      (node (ref "C209") (pin "2") (pinfunction "2_2") (pintype "passive"))
      (node (ref "C210") (pin "1") (pinfunction "1_1") (pintype "passive"))
      (node (ref "C211") (pin "2") (pinfunction "2_2") (pintype "passive"))
      (node (ref "C212") (pin "1") (pinfunction "1_1") (pintype "passive"))
      (node (ref "C213") (pin "2") (pinfunction "2_2") (pintype "passive"))
      (node (ref "C215") (pin "2") (pinfunction "2_2") (pintype "passive"))
      (node (ref "C217") (pin "2") (pinfunction "2_2") (pintype "passive"))
      (node (ref "C218") (pin "1") (pinfunction "1_1") (pintype "passive"))
      (node (ref "C219") (pin "1") (pinfunction "1_1") (pintype "passive"))
      (node (ref "C221") (pin "2") (pinfunction "2_2") (pintype "passive"))
      (node (ref "C222") (pin "2") (pinfunction "2_2") (pintype "passive"))
      (node (ref "C223") (pin "2") (pinfunction "2_2") (pintype "passive"))
      (node (ref "C224") (pin "2") (pinfunction "2_2") (pintype "passive"))
      (node (ref "D206") (pin "A") (pinfunction "A_A") (pintype "passive"))
      (node (ref "J203") (pin "5") (pinfunction "GND_5") (pintype "passive"))
      (node (ref "Q204") (pin "2") (pinfunction "2_2") (pintype "passive"))
      (node (ref "R210") (pin "2") (pinfunction "2_2") (pintype "passive"))
      (node (ref "R215") (pin "1") (pinfunction "1_1") (pintype "passive"))
      (node (ref "R227") (pin "2") (pinfunction "2_2") (pintype "passive"))
      (node (ref "R228") (pin "1") (pinfunction "1_1") (pintype "passive"))
      (node (ref "R229") (pin "1") (pinfunction "1_1") (pintype "passive"))
      (node (ref "R230") (pin "1") (pinfunction "1_1") (pintype "passive"))
      (node (ref "R235") (pin "2") (pinfunction "2_2") (pintype "passive"))
      (node (ref "R237") (pin "1") (pinfunction "1_1") (pintype "passive"))
      (node (ref "U200") (pin "2") (pinfunction "VN_2") (pintype "passive"))
      (node (ref "U201") (pin "20") (pinfunction "TESTMODE_20") (pintype "input"))
      (node (ref "U201") (pin "43") (pinfunction "RESERVED_43") (pintype "passive"))
      (node (ref "U201") (pin "44") (pinfunction "GND_44") (pintype "power_in"))
      (node (ref "U201") (pin "49") (pinfunction "EPAD_49") (pintype "passive"))
      (node (ref "U202") (pin "3") (pinfunction "GND_3") (pintype "passive"))
      (node (ref "U203") (pin "3") (pinfunction "GND_3") (pintype "passive"))
    )
    (net (code "51") (name "Net-(C208-Pad1)") (class "Default")
      (node (ref "C208") (pin "1") (pinfunction "1_1") (pintype "passive"))
      (node (ref "D201") (pin "A") (pinfunction "A_A") (pintype "passive"))
      (node (ref "R202") (pin "1") (pinfunction "1_1") (pintype "passive"))
    )
    (net (code "52") (name "Net-(D200-PadA)") (class "Default")
      (node (ref "D200") (pin "A") (pinfunction "A_A") (pintype "passive"))
      (node (ref "Q200") (pin "1") (pinfunction "1_1") (pintype "passive"))
      (node (ref "R200") (pin "2") (pinfunction "2_2") (pintype "passive"))
      (node (ref "R202") (pin "2") (pinfunction "2_2") (pintype "passive"))
    )
    (net (code "53") (name "Net-(D201-PadK)") (class "Default")
      (node (ref "D201") (pin "K") (pinfunction "K_K") (pintype "passive"))
      (node (ref "Q204") (pin "3") (pinfunction "3_3") (pintype "passive"))
      (node (ref "R201") (pin "2") (pinfunction "2_2") (pintype "passive"))
    )
    (net (code "54") (name "Net-(D202-PadK)") (class "Default")
      (node (ref "D202") (pin "K") (pinfunction "K_K") (pintype "passive"))
      (node (ref "D203") (pin "A") (pinfunction "A_A") (pintype "passive"))
      (node (ref "D204") (pin "K") (pinfunction "K_K") (pintype "passive"))
      (node (ref "D205") (pin "K") (pinfunction "K_K") (pintype "passive"))
    )
    (net (code "55") (name "Net-(D207-B)") (class "Default")
      (node (ref "D207") (pin "2") (pinfunction "B_2") (pintype "passive"))
      (node (ref "R240") (pin "1") (pinfunction "1_1") (pintype "passive"))
    )
    (net (code "56") (name "Net-(D207-G)") (class "Default")
      (node (ref "D207") (pin "3") (pinfunction "G_3") (pintype "passive"))
      (node (ref "R239") (pin "1") (pinfunction "1_1") (pintype "passive"))
    )
    (net (code "57") (name "Net-(D207-R)") (class "Default")
      (node (ref "D207") (pin "4") (pinfunction "R_4") (pintype "passive"))
      (node (ref "R236") (pin "1") (pinfunction "1_1") (pintype "passive"))
    )
    (net (code "58") (name "Net-(Q204-G)") (class "Default")
      (node (ref "Q204") (pin "1") (pinfunction "G_1") (pintype "passive"))
      (node (ref "R206") (pin "1") (pinfunction "1_1") (pintype "passive"))
      (node (ref "R210") (pin "1") (pinfunction "1_1") (pintype "passive"))
    )
    (net (code "59") (name "Net-(U200-IN+)") (class "Default")
      (node (ref "R220") (pin "2") (pinfunction "2_2") (pintype "passive"))
      (node (ref "R221") (pin "1") (pinfunction "1_1") (pintype "passive"))
      (node (ref "U200") (pin "1") (pinfunction "IN+_1") (pintype "passive"))
    )
    (net (code "60") (name "Net-(U200-IN-)") (class "Default")
      (node (ref "R226") (pin "1") (pinfunction "1_1") (pintype "passive"))
      (node (ref "R227") (pin "1") (pinfunction "1_1") (pintype "passive"))
      (node (ref "U200") (pin "3") (pinfunction "IN-_3") (pintype "passive"))
    )
    (net (code "61") (name "Net-(U200-OUT)") (class "Default")
      (node (ref "R224") (pin "1") (pinfunction "1_1") (pintype "passive"))
      (node (ref "R226") (pin "2") (pinfunction "2_2") (pintype "passive"))
      (node (ref "U200") (pin "4") (pinfunction "OUT_4") (pintype "passive"))
    )
    (net (code "62") (name "Net-(U201-NRST)") (class "Default")
      (node (ref "C221") (pin "1") (pinfunction "1_1") (pintype "passive"))
      (node (ref "R231") (pin "2") (pinfunction "2_2") (pintype "passive"))
      (node (ref "R232") (pin "2") (pinfunction "2_2") (pintype "passive"))
      (node (ref "U201") (pin "7") (pinfunction "NRST_7") (pintype "bidirectional"))
    )
    (net (code "63") (name "Net-(U201-PA5)") (class "Default")
      (node (ref "TP224") (pin "1") (pinfunction "1_1") (pintype "passive"))
      (node (ref "U201") (pin "16") (pinfunction "PA5_16") (pintype "bidirectional"))
    )
    (net (code "64") (name "Net-(U201-PA7)") (class "Default")
      (node (ref "TP225") (pin "1") (pinfunction "1_1") (pintype "passive"))
      (node (ref "U201") (pin "18") (pinfunction "PA7_18") (pintype "bidirectional"))
    )
    (net (code "65") (name "Net-(U201-PA15)") (class "Default")
      (node (ref "R217") (pin "2") (pinfunction "2_2") (pintype "passive"))
      (node (ref "U201") (pin "39") (pinfunction "PA15_39") (pintype "bidirectional"))
    )
    (net (code "66") (name "Net-(U201-PB6)") (class "Default")
      (node (ref "R223") (pin "2") (pinfunction "2_2") (pintype "passive"))
      (node (ref "U201") (pin "40") (pinfunction "PB6_40") (pintype "bidirectional"))
    )
    (net (code "67") (name "Net-(U201-PB7)") (class "Default")
      (node (ref "R222") (pin "2") (pinfunction "2_2") (pintype "passive"))
      (node (ref "U201") (pin "41") (pinfunction "PB7_41") (pintype "bidirectional"))
    )
    (net (code "68") (name "Net-(U201-SW)") (class "Default")
      (node (ref "D206") (pin "K") (pinfunction "K_K") (pintype "passive"))
      (node (ref "L200") (pin "1") (pinfunction "1_1") (pintype "passive"))
      (node (ref "U201") (pin "9") (pinfunction "SW_9") (pintype "output"))
    )
    (net (code "69") (name "Net-(U201-VBOOTU)") (class "Default")
      (node (ref "C214") (pin "1") (pinfunction "1_1") (pintype "passive"))
      (node (ref "U201") (pin "35") (pinfunction "VBOOTU_35") (pintype "power_in"))
    )
    (net (code "70") (name "Net-(U201-VBOOTV)") (class "Default")
      (node (ref "C216") (pin "1") (pinfunction "1_1") (pintype "passive"))
      (node (ref "U201") (pin "31") (pinfunction "VBOOTV_31") (pintype "power_in"))
    )
    (net (code "71") (name "Net-(U201-VBOOTW)") (class "Default")
      (node (ref "C220") (pin "1") (pinfunction "1_1") (pintype "passive"))
      (node (ref "U201") (pin "27") (pinfunction "VBOOTW_27") (pintype "power_in"))
    )
    (net (code "72") (name "Net-(U202-Y)") (class "Default")
      (node (ref "R234") (pin "1") (pinfunction "1_1") (pintype "passive"))
      (node (ref "U202") (pin "4") (pinfunction "Y_4") (pintype "passive"))
    )
    (net (code "73") (name "Net-(U203-Y)") (class "Default")
      (node (ref "R245") (pin "2") (pinfunction "2_2") (pintype "passive"))
      (node (ref "U203") (pin "4") (pinfunction "Y_4") (pintype "passive"))
    )
    (net (code "74") (name "Net-(U203-~{E})") (class "Default")
      (node (ref "R246") (pin "1") (pinfunction "1_1") (pintype "passive"))
      (node (ref "U203") (pin "1") (pinfunction "~{E}_1") (pintype "passive"))
    )
    (net (code "75") (name "VBAT") (class "Default")
      (node (ref "C201") (pin "1") (pinfunction "1_1") (pintype "passive"))
      (node (ref "C202") (pin "1") (pinfunction "1_1") (pintype "passive"))
      (node (ref "C203") (pin "1") (pinfunction "1_1") (pintype "passive"))
      (node (ref "C204") (pin "1") (pinfunction "1_1") (pintype "passive"))
      (node (ref "C205") (pin "1") (pinfunction "1_1") (pintype "passive"))
      (node (ref "C206") (pin "1") (pinfunction "1_1") (pintype "passive"))
      (node (ref "D200") (pin "K") (pinfunction "K_K") (pintype "passive"))
      (node (ref "Q200") (pin "2") (pinfunction "2_2") (pintype "passive"))
      (node (ref "Q201") (pin "5") (pinfunction "D_5") (pintype "passive"))
      (node (ref "Q201") (pin "6") (pinfunction "D_6") (pintype "passive"))
      (node (ref "Q201") (pin "7") (pinfunction "D_7") (pintype "passive"))
      (node (ref "Q201") (pin "8") (pinfunction "D_8") (pintype "passive"))
      (node (ref "Q202") (pin "5") (pinfunction "D_5") (pintype "passive"))
      (node (ref "Q202") (pin "6") (pinfunction "D_6") (pintype "passive"))
      (node (ref "Q202") (pin "7") (pinfunction "D_7") (pintype "passive"))
      (node (ref "Q202") (pin "8") (pinfunction "D_8") (pintype "passive"))
      (node (ref "Q203") (pin "5") (pinfunction "D_5") (pintype "passive"))
      (node (ref "Q203") (pin "6") (pinfunction "D_6") (pintype "passive"))
      (node (ref "Q203") (pin "7") (pinfunction "D_7") (pintype "passive"))
      (node (ref "Q203") (pin "8") (pinfunction "D_8") (pintype "passive"))
      (node (ref "R200") (pin "1") (pinfunction "1_1") (pintype "passive"))
      (node (ref "R201") (pin "1") (pinfunction "1_1") (pintype "passive"))
      (node (ref "R233") (pin "1") (pinfunction "1_1") (pintype "passive"))
    )
    (net (code "76") (name "unconnected-(J203-SWO-Pad6)") (class "Default")
      (node (ref "J203") (pin "6") (pinfunction "SWO_6") (pintype "passive"))
    )
    (net (code "77") (name "unconnected-(J203-nRESET-Pad3)") (class "Default")
      (node (ref "J203") (pin "3") (pinfunction "nRESET_3") (pintype "passive"))
    )
  )
)
